# grbl_pendant_peripheral.net
KiCad netlist of a schematic drawn in EAGLE
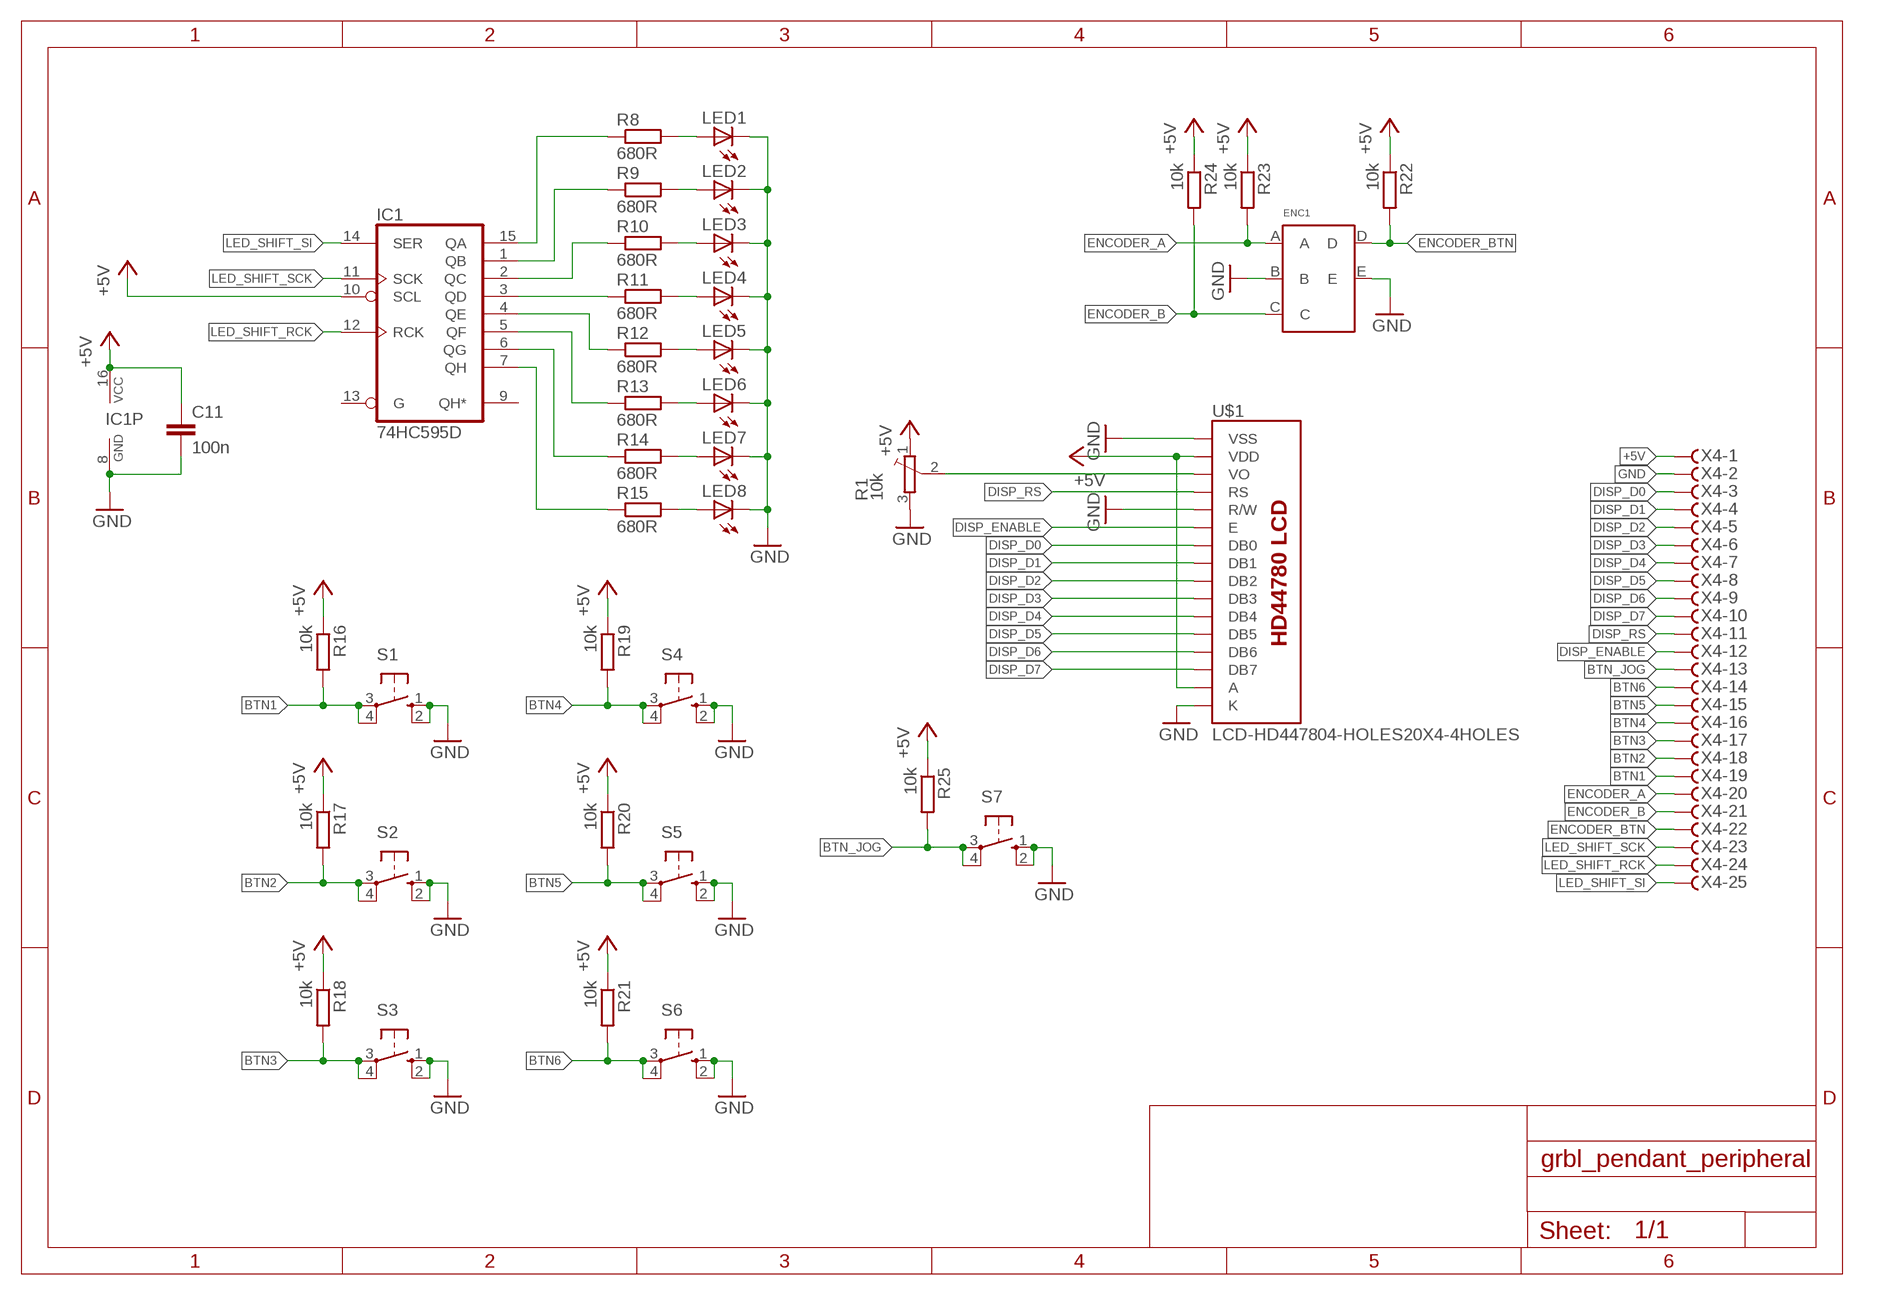
[diagram p0: schematic, sheet 1]

(export (version "E")
  (design (tool "Eeschema 10.0.6"))
  (components
    (comp (ref "C11")
      (value "100n")
      (footprint "eagle-import:C0603K")
      (libsource (lib "eagle-import") (part "C-EUC0603K"))
    )
    (comp (ref "ENC1")
      (value "ENCODER")
      (footprint "eagle-import:ENCODER")
      (libsource (lib "eagle-import") (part "ENCODER"))
    )
    (comp (ref "IC1")
      (value "74HC595D")
      (footprint "eagle-import:SO16")
      (libsource (lib "eagle-import") (part "74595DHC"))
    )
    (comp (ref "LED1")
      (value "LED5MM")
      (footprint "eagle-import:LED5MM")
      (libsource (lib "eagle-import") (part "LED5MM"))
    )
    (comp (ref "LED2")
      (value "LED5MM")
      (footprint "eagle-import:LED5MM")
      (libsource (lib "eagle-import") (part "LED5MM"))
    )
    (comp (ref "LED3")
      (value "LED5MM")
      (footprint "eagle-import:LED5MM")
      (libsource (lib "eagle-import") (part "LED5MM"))
    )
    (comp (ref "LED4")
      (value "LED5MM")
      (footprint "eagle-import:LED5MM")
      (libsource (lib "eagle-import") (part "LED5MM"))
    )
    (comp (ref "LED5")
      (value "LED5MM")
      (footprint "eagle-import:LED5MM")
      (libsource (lib "eagle-import") (part "LED5MM"))
    )
    (comp (ref "LED6")
      (value "LED5MM")
      (footprint "eagle-import:LED5MM")
      (libsource (lib "eagle-import") (part "LED5MM"))
    )
    (comp (ref "LED7")
      (value "LED5MM")
      (footprint "eagle-import:LED5MM")
      (libsource (lib "eagle-import") (part "LED5MM"))
    )
    (comp (ref "LED8")
      (value "LED5MM")
      (footprint "eagle-import:LED5MM")
      (libsource (lib "eagle-import") (part "LED5MM"))
    )
    (comp (ref "R1")
      (value "10k")
      (footprint "eagle-import:35WR5KLFTR")
      (libsource (lib "eagle-import") (part "35WR5KLFTR"))
    )
    (comp (ref "R8")
      (value "680R")
      (footprint "eagle-import:R0603")
      (libsource (lib "eagle-import") (part "R-EU_R0603"))
    )
    (comp (ref "R9")
      (value "680R")
      (footprint "eagle-import:R0603")
      (libsource (lib "eagle-import") (part "R-EU_R0603"))
    )
    (comp (ref "R10")
      (value "680R")
      (footprint "eagle-import:R0603")
      (libsource (lib "eagle-import") (part "R-EU_R0603"))
    )
    (comp (ref "R11")
      (value "680R")
      (footprint "eagle-import:R0603")
      (libsource (lib "eagle-import") (part "R-EU_R0603"))
    )
    (comp (ref "R12")
      (value "680R")
      (footprint "eagle-import:R0603")
      (libsource (lib "eagle-import") (part "R-EU_R0603"))
    )
    (comp (ref "R13")
      (value "680R")
      (footprint "eagle-import:R0603")
      (libsource (lib "eagle-import") (part "R-EU_R0603"))
    )
    (comp (ref "R14")
      (value "680R")
      (footprint "eagle-import:R0603")
      (libsource (lib "eagle-import") (part "R-EU_R0603"))
    )
    (comp (ref "R15")
      (value "680R")
      (footprint "eagle-import:R0603")
      (libsource (lib "eagle-import") (part "R-EU_R0603"))
    )
    (comp (ref "R16")
      (value "10k")
      (footprint "eagle-import:R0603")
      (libsource (lib "eagle-import") (part "R-EU_R0603"))
    )
    (comp (ref "R17")
      (value "10k")
      (footprint "eagle-import:R0603")
      (libsource (lib "eagle-import") (part "R-EU_R0603"))
    )
    (comp (ref "R18")
      (value "10k")
      (footprint "eagle-import:R0603")
      (libsource (lib "eagle-import") (part "R-EU_R0603"))
    )
    (comp (ref "R19")
      (value "10k")
      (footprint "eagle-import:R0603")
      (libsource (lib "eagle-import") (part "R-EU_R0603"))
    )
    (comp (ref "R20")
      (value "10k")
      (footprint "eagle-import:R0603")
      (libsource (lib "eagle-import") (part "R-EU_R0603"))
    )
    (comp (ref "R21")
      (value "10k")
      (footprint "eagle-import:R0603")
      (libsource (lib "eagle-import") (part "R-EU_R0603"))
    )
    (comp (ref "R22")
      (value "10k")
      (footprint "eagle-import:R0603")
      (libsource (lib "eagle-import") (part "R-EU_R0603"))
    )
    (comp (ref "R23")
      (value "10k")
      (footprint "eagle-import:R0603")
      (libsource (lib "eagle-import") (part "R-EU_R0603"))
    )
    (comp (ref "R24")
      (value "10k")
      (footprint "eagle-import:R0603")
      (libsource (lib "eagle-import") (part "R-EU_R0603"))
    )
    (comp (ref "R25")
      (value "10k")
      (footprint "eagle-import:R0603")
      (libsource (lib "eagle-import") (part "R-EU_R0603"))
    )
    (comp (ref "S1")
      (value "10-XX")
      (footprint "eagle-import:B3F-10XX")
      (fields (field (name "MPN") "B3F-1000"))
      (libsource (lib "eagle-import") (part "10-XX"))
    )
    (comp (ref "S2")
      (value "10-XX")
      (footprint "eagle-import:B3F-10XX")
      (fields (field (name "MPN") "B3F-1000"))
      (libsource (lib "eagle-import") (part "10-XX"))
    )
    (comp (ref "S3")
      (value "10-XX")
      (footprint "eagle-import:B3F-10XX")
      (fields (field (name "MPN") "B3F-1000"))
      (libsource (lib "eagle-import") (part "10-XX"))
    )
    (comp (ref "S4")
      (value "10-XX")
      (footprint "eagle-import:B3F-10XX")
      (fields (field (name "MPN") "B3F-1000"))
      (libsource (lib "eagle-import") (part "10-XX"))
    )
    (comp (ref "S5")
      (value "10-XX")
      (footprint "eagle-import:B3F-10XX")
      (fields (field (name "MPN") "B3F-1000"))
      (libsource (lib "eagle-import") (part "10-XX"))
    )
    (comp (ref "S6")
      (value "10-XX")
      (footprint "eagle-import:B3F-10XX")
      (fields (field (name "MPN") "B3F-1000"))
      (libsource (lib "eagle-import") (part "10-XX"))
    )
    (comp (ref "S7")
      (value "10-XX")
      (footprint "eagle-import:B3F-10XX")
      (fields (field (name "MPN") "B3F-1000"))
      (libsource (lib "eagle-import") (part "10-XX"))
    )
    (comp (ref "U$1")
      (value "LCD-HD447804-HOLES20X4-4HOLES")
      (footprint "eagle-import:LCD-20X4-4HOLES")
      (libsource (lib "eagle-import") (part "LCD-HD4478020X4-4HOLES4-HOLES"))
    )
    (comp (ref "X4")
      (value "F25HPS")
      (footprint "eagle-import:F25HP")
      (libsource (lib "eagle-import") (part "F25?SHP"))
    )
  )
  (nets
    (net (code "1") (name "+5V") (class "Default")
      (node (ref "C11") (pin "1") (pinfunction "1_1") (pintype "passive"))
      (node (ref "IC1") (pin "10") (pinfunction "SCL_10") (pintype "input"))
      (node (ref "IC1") (pin "16") (pinfunction "VCC_16") (pintype "power_in"))
      (node (ref "R1") (pin "1") (pinfunction "E_1") (pintype "passive"))
      (node (ref "R16") (pin "1") (pinfunction "1_1") (pintype "passive"))
      (node (ref "R17") (pin "1") (pinfunction "1_1") (pintype "passive"))
      (node (ref "R18") (pin "1") (pinfunction "1_1") (pintype "passive"))
      (node (ref "R19") (pin "1") (pinfunction "1_1") (pintype "passive"))
      (node (ref "R20") (pin "1") (pinfunction "1_1") (pintype "passive"))
      (node (ref "R21") (pin "1") (pinfunction "1_1") (pintype "passive"))
      (node (ref "R22") (pin "1") (pinfunction "1_1") (pintype "passive"))
      (node (ref "R23") (pin "1") (pinfunction "1_1") (pintype "passive"))
      (node (ref "R24") (pin "1") (pinfunction "1_1") (pintype "passive"))
      (node (ref "R25") (pin "1") (pinfunction "1_1") (pintype "passive"))
      (node (ref "U$1") (pin "P$15") (pinfunction "A_P$15") (pintype "power_in"))
      (node (ref "U$1") (pin "P$2") (pinfunction "VDD_P$2") (pintype "power_in"))
      (node (ref "X4") (pin "1") (pinfunction "F_1") (pintype "passive"))
    )
    (net (code "2") (name "BTN1") (class "Default")
      (node (ref "R16") (pin "2") (pinfunction "2_2") (pintype "passive"))
      (node (ref "S1") (pin "3") (pinfunction "P_3") (pintype "passive"))
      (node (ref "S1") (pin "4") (pinfunction "P1_4") (pintype "passive"))
      (node (ref "X4") (pin "19") (pinfunction "F_19") (pintype "passive"))
    )
    (net (code "3") (name "BTN2") (class "Default")
      (node (ref "R17") (pin "2") (pinfunction "2_2") (pintype "passive"))
      (node (ref "S2") (pin "3") (pinfunction "P_3") (pintype "passive"))
      (node (ref "S2") (pin "4") (pinfunction "P1_4") (pintype "passive"))
      (node (ref "X4") (pin "18") (pinfunction "F_18") (pintype "passive"))
    )
    (net (code "4") (name "BTN3") (class "Default")
      (node (ref "R18") (pin "2") (pinfunction "2_2") (pintype "passive"))
      (node (ref "S3") (pin "3") (pinfunction "P_3") (pintype "passive"))
      (node (ref "S3") (pin "4") (pinfunction "P1_4") (pintype "passive"))
      (node (ref "X4") (pin "17") (pinfunction "F_17") (pintype "passive"))
    )
    (net (code "5") (name "BTN4") (class "Default")
      (node (ref "R19") (pin "2") (pinfunction "2_2") (pintype "passive"))
      (node (ref "S4") (pin "3") (pinfunction "P_3") (pintype "passive"))
      (node (ref "S4") (pin "4") (pinfunction "P1_4") (pintype "passive"))
      (node (ref "X4") (pin "16") (pinfunction "F_16") (pintype "passive"))
    )
    (net (code "6") (name "BTN5") (class "Default")
      (node (ref "R20") (pin "2") (pinfunction "2_2") (pintype "passive"))
      (node (ref "S5") (pin "3") (pinfunction "P_3") (pintype "passive"))
      (node (ref "S5") (pin "4") (pinfunction "P1_4") (pintype "passive"))
      (node (ref "X4") (pin "15") (pinfunction "F_15") (pintype "passive"))
    )
    (net (code "7") (name "BTN6") (class "Default")
      (node (ref "R21") (pin "2") (pinfunction "2_2") (pintype "passive"))
      (node (ref "S6") (pin "3") (pinfunction "P_3") (pintype "passive"))
      (node (ref "S6") (pin "4") (pinfunction "P1_4") (pintype "passive"))
      (node (ref "X4") (pin "14") (pinfunction "F_14") (pintype "passive"))
    )
    (net (code "8") (name "BTN_JOG") (class "Default")
      (node (ref "R25") (pin "2") (pinfunction "2_2") (pintype "passive"))
      (node (ref "S7") (pin "3") (pinfunction "P_3") (pintype "passive"))
      (node (ref "S7") (pin "4") (pinfunction "P1_4") (pintype "passive"))
      (node (ref "X4") (pin "13") (pinfunction "F_13") (pintype "passive"))
    )
    (net (code "9") (name "DISP_D0") (class "Default")
      (node (ref "U$1") (pin "P$7") (pinfunction "DB0_P$7") (pintype "bidirectional"))
      (node (ref "X4") (pin "3") (pinfunction "F_3") (pintype "passive"))
    )
    (net (code "10") (name "DISP_D1") (class "Default")
      (node (ref "U$1") (pin "P$8") (pinfunction "DB1_P$8") (pintype "bidirectional"))
      (node (ref "X4") (pin "4") (pinfunction "F_4") (pintype "passive"))
    )
    (net (code "11") (name "DISP_D2") (class "Default")
      (node (ref "U$1") (pin "P$9") (pinfunction "DB2_P$9") (pintype "bidirectional"))
      (node (ref "X4") (pin "5") (pinfunction "F_5") (pintype "passive"))
    )
    (net (code "12") (name "DISP_D3") (class "Default")
      (node (ref "U$1") (pin "P$10") (pinfunction "DB3_P$10") (pintype "bidirectional"))
      (node (ref "X4") (pin "6") (pinfunction "F_6") (pintype "passive"))
    )
    (net (code "13") (name "DISP_D4") (class "Default")
      (node (ref "U$1") (pin "P$11") (pinfunction "DB4_P$11") (pintype "bidirectional"))
      (node (ref "X4") (pin "7") (pinfunction "F_7") (pintype "passive"))
    )
    (net (code "14") (name "DISP_D5") (class "Default")
      (node (ref "U$1") (pin "P$12") (pinfunction "DB5_P$12") (pintype "bidirectional"))
      (node (ref "X4") (pin "8") (pinfunction "F_8") (pintype "passive"))
    )
    (net (code "15") (name "DISP_D6") (class "Default")
      (node (ref "U$1") (pin "P$13") (pinfunction "DB6_P$13") (pintype "bidirectional"))
      (node (ref "X4") (pin "9") (pinfunction "F_9") (pintype "passive"))
    )
    (net (code "16") (name "DISP_D7") (class "Default")
      (node (ref "U$1") (pin "P$14") (pinfunction "DB7_P$14") (pintype "bidirectional"))
      (node (ref "X4") (pin "10") (pinfunction "F_10") (pintype "passive"))
    )
    (net (code "17") (name "DISP_ENABLE") (class "Default")
      (node (ref "U$1") (pin "P$6") (pinfunction "E_P$6") (pintype "input"))
      (node (ref "X4") (pin "12") (pinfunction "F_12") (pintype "passive"))
    )
    (net (code "18") (name "DISP_RS") (class "Default")
      (node (ref "U$1") (pin "P$4") (pinfunction "RS_P$4") (pintype "input"))
      (node (ref "X4") (pin "11") (pinfunction "F_11") (pintype "passive"))
    )
    (net (code "19") (name "ENCODER_A") (class "Default")
      (node (ref "ENC1") (pin "A") (pinfunction "A_A") (pintype "output"))
      (node (ref "R23") (pin "2") (pinfunction "2_2") (pintype "passive"))
      (node (ref "X4") (pin "20") (pinfunction "F_20") (pintype "passive"))
    )
    (net (code "20") (name "ENCODER_B") (class "Default")
      (node (ref "ENC1") (pin "C") (pinfunction "C_C") (pintype "power_in"))
      (node (ref "R24") (pin "2") (pinfunction "2_2") (pintype "passive"))
      (node (ref "X4") (pin "21") (pinfunction "F_21") (pintype "passive"))
    )
    (net (code "21") (name "ENCODER_BTN") (class "Default")
      (node (ref "ENC1") (pin "D") (pinfunction "D_D") (pintype "output"))
      (node (ref "R22") (pin "2") (pinfunction "2_2") (pintype "passive"))
      (node (ref "X4") (pin "22") (pinfunction "F_22") (pintype "passive"))
    )
    (net (code "22") (name "GND") (class "Default")
      (node (ref "C11") (pin "2") (pinfunction "2_2") (pintype "passive"))
      (node (ref "ENC1") (pin "B") (pinfunction "B_B") (pintype "output"))
      (node (ref "ENC1") (pin "E") (pinfunction "E_E") (pintype "power_in"))
      (node (ref "IC1") (pin "8") (pinfunction "GND_8") (pintype "power_in"))
      (node (ref "LED1") (pin "K") (pinfunction "C_K") (pintype "passive"))
      (node (ref "LED2") (pin "K") (pinfunction "C_K") (pintype "passive"))
      (node (ref "LED3") (pin "K") (pinfunction "C_K") (pintype "passive"))
      (node (ref "LED4") (pin "K") (pinfunction "C_K") (pintype "passive"))
      (node (ref "LED5") (pin "K") (pinfunction "C_K") (pintype "passive"))
      (node (ref "LED6") (pin "K") (pinfunction "C_K") (pintype "passive"))
      (node (ref "LED7") (pin "K") (pinfunction "C_K") (pintype "passive"))
      (node (ref "LED8") (pin "K") (pinfunction "C_K") (pintype "passive"))
      (node (ref "R1") (pin "3") (pinfunction "A_3") (pintype "passive"))
      (node (ref "S1") (pin "1") (pinfunction "S_1") (pintype "passive"))
      (node (ref "S1") (pin "2") (pinfunction "S1_2") (pintype "passive"))
      (node (ref "S2") (pin "1") (pinfunction "S_1") (pintype "passive"))
      (node (ref "S2") (pin "2") (pinfunction "S1_2") (pintype "passive"))
      (node (ref "S3") (pin "1") (pinfunction "S_1") (pintype "passive"))
      (node (ref "S3") (pin "2") (pinfunction "S1_2") (pintype "passive"))
      (node (ref "S4") (pin "1") (pinfunction "S_1") (pintype "passive"))
      (node (ref "S4") (pin "2") (pinfunction "S1_2") (pintype "passive"))
      (node (ref "S5") (pin "1") (pinfunction "S_1") (pintype "passive"))
      (node (ref "S5") (pin "2") (pinfunction "S1_2") (pintype "passive"))
      (node (ref "S6") (pin "1") (pinfunction "S_1") (pintype "passive"))
      (node (ref "S6") (pin "2") (pinfunction "S1_2") (pintype "passive"))
      (node (ref "S7") (pin "1") (pinfunction "S_1") (pintype "passive"))
      (node (ref "S7") (pin "2") (pinfunction "S1_2") (pintype "passive"))
      (node (ref "U$1") (pin "P$1") (pinfunction "VSS_P$1") (pintype "power_in"))
      (node (ref "U$1") (pin "P$16") (pinfunction "K_P$16") (pintype "power_in"))
      (node (ref "U$1") (pin "P$5") (pinfunction "R/W_P$5") (pintype "input"))
      (node (ref "X4") (pin "2") (pinfunction "F_2") (pintype "passive"))
    )
    (net (code "23") (name "LED_SHIFT_RCK") (class "Default")
      (node (ref "IC1") (pin "12") (pinfunction "RCK_12") (pintype "input"))
      (node (ref "X4") (pin "24") (pinfunction "F_24") (pintype "passive"))
    )
    (net (code "24") (name "LED_SHIFT_SCK") (class "Default")
      (node (ref "IC1") (pin "11") (pinfunction "SCK_11") (pintype "input"))
      (node (ref "X4") (pin "23") (pinfunction "F_23") (pintype "passive"))
    )
    (net (code "25") (name "LED_SHIFT_SI") (class "Default")
      (node (ref "IC1") (pin "14") (pinfunction "SER_14") (pintype "input"))
      (node (ref "X4") (pin "25") (pinfunction "F_25") (pintype "passive"))
    )
    (net (code "26") (name "Net-(IC1A-QA)") (class "Default")
      (node (ref "IC1") (pin "15") (pinfunction "QA_15") (pintype "tri_state"))
      (node (ref "R8") (pin "1") (pinfunction "1_1") (pintype "passive"))
    )
    (net (code "27") (name "Net-(IC1A-QB)") (class "Default")
      (node (ref "IC1") (pin "1") (pinfunction "QB_1") (pintype "tri_state"))
      (node (ref "R9") (pin "1") (pinfunction "1_1") (pintype "passive"))
    )
    (net (code "28") (name "Net-(IC1A-QC)") (class "Default")
      (node (ref "IC1") (pin "2") (pinfunction "QC_2") (pintype "tri_state"))
      (node (ref "R10") (pin "1") (pinfunction "1_1") (pintype "passive"))
    )
    (net (code "29") (name "Net-(IC1A-QD)") (class "Default")
      (node (ref "IC1") (pin "3") (pinfunction "QD_3") (pintype "tri_state"))
      (node (ref "R11") (pin "1") (pinfunction "1_1") (pintype "passive"))
    )
    (net (code "30") (name "Net-(IC1A-QE)") (class "Default")
      (node (ref "IC1") (pin "4") (pinfunction "QE_4") (pintype "tri_state"))
      (node (ref "R12") (pin "1") (pinfunction "1_1") (pintype "passive"))
    )
    (net (code "31") (name "Net-(IC1A-QF)") (class "Default")
      (node (ref "IC1") (pin "5") (pinfunction "QF_5") (pintype "tri_state"))
      (node (ref "R13") (pin "1") (pinfunction "1_1") (pintype "passive"))
    )
    (net (code "32") (name "Net-(IC1A-QG)") (class "Default")
      (node (ref "IC1") (pin "6") (pinfunction "QG_6") (pintype "tri_state"))
      (node (ref "R14") (pin "1") (pinfunction "1_1") (pintype "passive"))
    )
    (net (code "33") (name "Net-(IC1A-QH)") (class "Default")
      (node (ref "IC1") (pin "7") (pinfunction "QH_7") (pintype "tri_state"))
      (node (ref "R15") (pin "1") (pinfunction "1_1") (pintype "passive"))
    )
    (net (code "34") (name "Net-(LED1-PadA)") (class "Default")
      (node (ref "LED1") (pin "A") (pinfunction "A_A") (pintype "passive"))
      (node (ref "R8") (pin "2") (pinfunction "2_2") (pintype "passive"))
    )
    (net (code "35") (name "Net-(LED2-PadA)") (class "Default")
      (node (ref "LED2") (pin "A") (pinfunction "A_A") (pintype "passive"))
      (node (ref "R9") (pin "2") (pinfunction "2_2") (pintype "passive"))
    )
    (net (code "36") (name "Net-(LED3-PadA)") (class "Default")
      (node (ref "LED3") (pin "A") (pinfunction "A_A") (pintype "passive"))
      (node (ref "R10") (pin "2") (pinfunction "2_2") (pintype "passive"))
    )
    (net (code "37") (name "Net-(LED4-PadA)") (class "Default")
      (node (ref "LED4") (pin "A") (pinfunction "A_A") (pintype "passive"))
      (node (ref "R11") (pin "2") (pinfunction "2_2") (pintype "passive"))
    )
    (net (code "38") (name "Net-(LED5-PadA)") (class "Default")
      (node (ref "LED5") (pin "A") (pinfunction "A_A") (pintype "passive"))
      (node (ref "R12") (pin "2") (pinfunction "2_2") (pintype "passive"))
    )
    (net (code "39") (name "Net-(LED6-PadA)") (class "Default")
      (node (ref "LED6") (pin "A") (pinfunction "A_A") (pintype "passive"))
      (node (ref "R13") (pin "2") (pinfunction "2_2") (pintype "passive"))
    )
    (net (code "40") (name "Net-(LED7-PadA)") (class "Default")
      (node (ref "LED7") (pin "A") (pinfunction "A_A") (pintype "passive"))
      (node (ref "R14") (pin "2") (pinfunction "2_2") (pintype "passive"))
    )
    (net (code "41") (name "Net-(LED8-PadA)") (class "Default")
      (node (ref "LED8") (pin "A") (pinfunction "A_A") (pintype "passive"))
      (node (ref "R15") (pin "2") (pinfunction "2_2") (pintype "passive"))
    )
    (net (code "42") (name "Net-(R1-S)") (class "Default")
      (node (ref "R1") (pin "2") (pinfunction "S_2") (pintype "passive"))
      (node (ref "U$1") (pin "P$3") (pinfunction "VO_P$3") (pintype "bidirectional"))
    )
    (net (code "43") (name "unconnected-(IC1A-G-Pad13)") (class "Default")
      (node (ref "IC1") (pin "13") (pinfunction "G_13") (pintype "input"))
    )
    (net (code "44") (name "unconnected-(IC1A-QH*-Pad9)") (class "Default")
      (node (ref "IC1") (pin "9") (pinfunction "QH*_9") (pintype "tri_state"))
    )
  )
)
